# TopSolarPanel.net
KiCad netlist of a schematic drawn in EAGLE
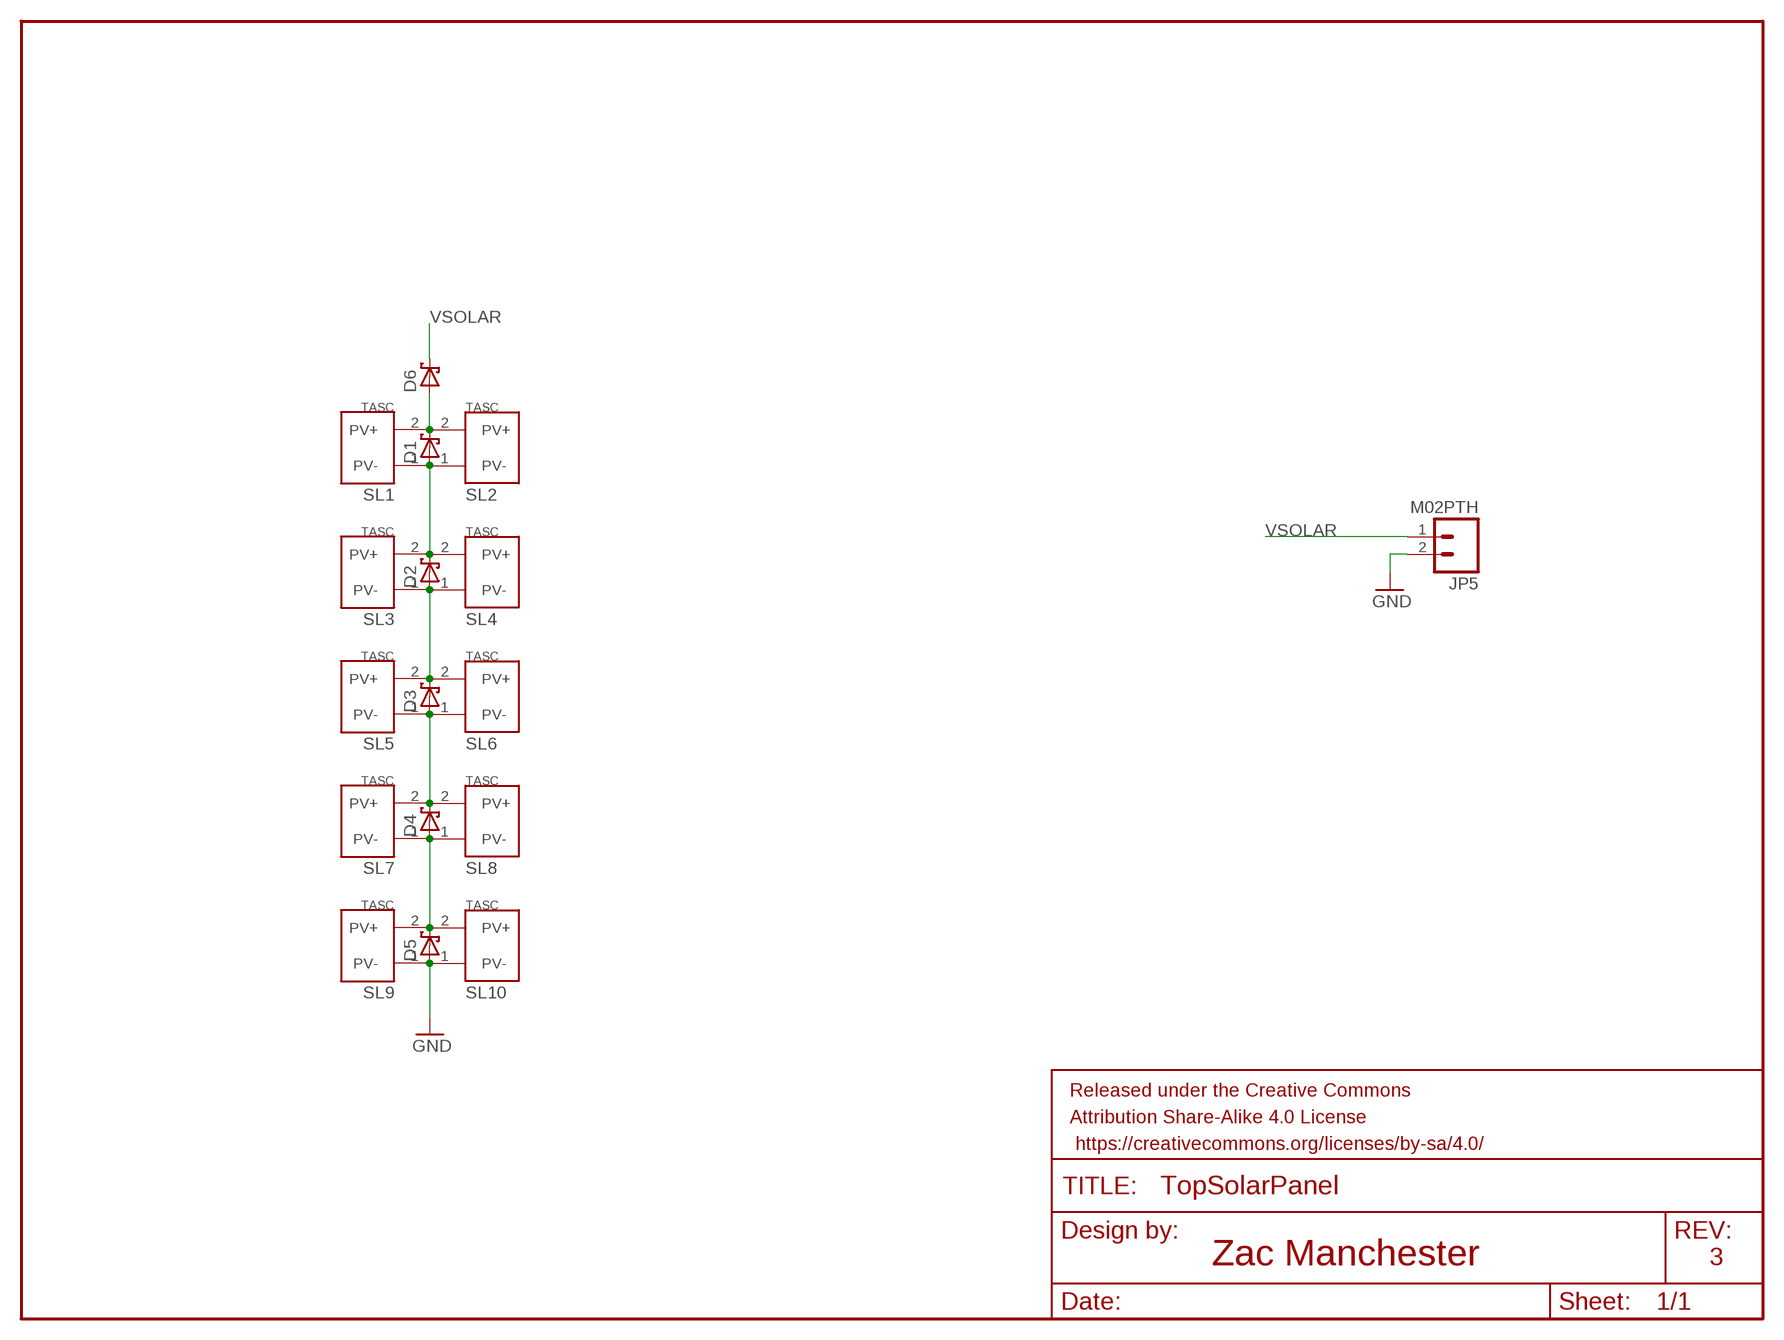
[diagram p0: schematic, sheet 1]

(export (version "E")
  (design (tool "Eeschema 10.0.6"))
  (components
    (comp (ref "D1")
      (value "SB_DIODE")
      (footprint "eagle-import:SB_DIODE")
      (libsource (lib "eagle-import") (part "SB_DIODE"))
    )
    (comp (ref "D2")
      (value "SB_DIODE")
      (footprint "eagle-import:SB_DIODE")
      (libsource (lib "eagle-import") (part "SB_DIODE"))
    )
    (comp (ref "D3")
      (value "SB_DIODE")
      (footprint "eagle-import:SB_DIODE")
      (libsource (lib "eagle-import") (part "SB_DIODE"))
    )
    (comp (ref "D4")
      (value "SB_DIODE")
      (footprint "eagle-import:SB_DIODE")
      (libsource (lib "eagle-import") (part "SB_DIODE"))
    )
    (comp (ref "D5")
      (value "SB_DIODE")
      (footprint "eagle-import:SB_DIODE")
      (libsource (lib "eagle-import") (part "SB_DIODE"))
    )
    (comp (ref "D6")
      (value "SB_DIODE")
      (footprint "eagle-import:SB_DIODE")
      (libsource (lib "eagle-import") (part "SB_DIODE"))
    )
    (comp (ref "FRAME1")
      (value "FRAME-LETTER")
      (footprint "eagle-import:CREATIVE_COMMONS")
      (libsource (lib "eagle-import") (part "FRAME-LETTER"))
    )
    (comp (ref "JP5")
      (value "M02PTH")
      (footprint "eagle-import:1X02")
      (libsource (lib "eagle-import") (part "M02PTH"))
    )
    (comp (ref "SL1")
      (value "SOLAR_CELL")
      (footprint "eagle-import:SOLAR_CELL")
      (libsource (lib "eagle-import") (part "SOLAR_CELL"))
    )
    (comp (ref "SL2")
      (value "SOLAR_CELL")
      (footprint "eagle-import:SOLAR_CELL")
      (libsource (lib "eagle-import") (part "SOLAR_CELL"))
    )
    (comp (ref "SL3")
      (value "SOLAR_CELL")
      (footprint "eagle-import:SOLAR_CELL")
      (libsource (lib "eagle-import") (part "SOLAR_CELL"))
    )
    (comp (ref "SL4")
      (value "SOLAR_CELL")
      (footprint "eagle-import:SOLAR_CELL")
      (libsource (lib "eagle-import") (part "SOLAR_CELL"))
    )
    (comp (ref "SL5")
      (value "SOLAR_CELL")
      (footprint "eagle-import:SOLAR_CELL")
      (libsource (lib "eagle-import") (part "SOLAR_CELL"))
    )
    (comp (ref "SL6")
      (value "SOLAR_CELL")
      (footprint "eagle-import:SOLAR_CELL")
      (libsource (lib "eagle-import") (part "SOLAR_CELL"))
    )
    (comp (ref "SL7")
      (value "SOLAR_CELL")
      (footprint "eagle-import:SOLAR_CELL")
      (libsource (lib "eagle-import") (part "SOLAR_CELL"))
    )
    (comp (ref "SL8")
      (value "SOLAR_CELL")
      (footprint "eagle-import:SOLAR_CELL")
      (libsource (lib "eagle-import") (part "SOLAR_CELL"))
    )
    (comp (ref "SL9")
      (value "SOLAR_CELL")
      (footprint "eagle-import:SOLAR_CELL")
      (libsource (lib "eagle-import") (part "SOLAR_CELL"))
    )
    (comp (ref "SL10")
      (value "SOLAR_CELL")
      (footprint "eagle-import:SOLAR_CELL")
      (libsource (lib "eagle-import") (part "SOLAR_CELL"))
    )
  )
  (nets
    (net (code "1") (name "/VSOLAR") (class "Default")
      (node (ref "D6") (pin "NEG") (pinfunction "NEG_NEG") (pintype "passive"))
      (node (ref "JP5") (pin "1") (pinfunction "1_1") (pintype "passive"))
    )
    (net (code "2") (name "GND") (class "Default")
      (node (ref "D5") (pin "POS") (pinfunction "POS_POS") (pintype "passive"))
      (node (ref "JP5") (pin "2") (pinfunction "2_2") (pintype "passive"))
      (node (ref "SL10") (pin "1") (pinfunction "PV-_1") (pintype "bidirectional"))
      (node (ref "SL9") (pin "1") (pinfunction "PV-_1") (pintype "bidirectional"))
    )
    (net (code "3") (name "Net-(SL1-PV+)") (class "Default")
      (node (ref "D1") (pin "NEG") (pinfunction "NEG_NEG") (pintype "passive"))
      (node (ref "D6") (pin "POS") (pinfunction "POS_POS") (pintype "passive"))
      (node (ref "SL1") (pin "2") (pinfunction "PV+_2") (pintype "bidirectional"))
      (node (ref "SL2") (pin "2") (pinfunction "PV+_2") (pintype "bidirectional"))
    )
    (net (code "4") (name "Net-(SL1-PV-)") (class "Default")
      (node (ref "D1") (pin "POS") (pinfunction "POS_POS") (pintype "passive"))
      (node (ref "D2") (pin "NEG") (pinfunction "NEG_NEG") (pintype "passive"))
      (node (ref "SL1") (pin "1") (pinfunction "PV-_1") (pintype "bidirectional"))
      (node (ref "SL2") (pin "1") (pinfunction "PV-_1") (pintype "bidirectional"))
      (node (ref "SL3") (pin "2") (pinfunction "PV+_2") (pintype "bidirectional"))
      (node (ref "SL4") (pin "2") (pinfunction "PV+_2") (pintype "bidirectional"))
    )
    (net (code "5") (name "Net-(SL3-PV-)") (class "Default")
      (node (ref "D2") (pin "POS") (pinfunction "POS_POS") (pintype "passive"))
      (node (ref "D3") (pin "NEG") (pinfunction "NEG_NEG") (pintype "passive"))
      (node (ref "SL3") (pin "1") (pinfunction "PV-_1") (pintype "bidirectional"))
      (node (ref "SL4") (pin "1") (pinfunction "PV-_1") (pintype "bidirectional"))
      (node (ref "SL5") (pin "2") (pinfunction "PV+_2") (pintype "bidirectional"))
      (node (ref "SL6") (pin "2") (pinfunction "PV+_2") (pintype "bidirectional"))
    )
    (net (code "6") (name "Net-(SL5-PV-)") (class "Default")
      (node (ref "D3") (pin "POS") (pinfunction "POS_POS") (pintype "passive"))
      (node (ref "D4") (pin "NEG") (pinfunction "NEG_NEG") (pintype "passive"))
      (node (ref "SL5") (pin "1") (pinfunction "PV-_1") (pintype "bidirectional"))
      (node (ref "SL6") (pin "1") (pinfunction "PV-_1") (pintype "bidirectional"))
      (node (ref "SL7") (pin "2") (pinfunction "PV+_2") (pintype "bidirectional"))
      (node (ref "SL8") (pin "2") (pinfunction "PV+_2") (pintype "bidirectional"))
    )
    (net (code "7") (name "Net-(SL10-PV+)") (class "Default")
      (node (ref "D4") (pin "POS") (pinfunction "POS_POS") (pintype "passive"))
      (node (ref "D5") (pin "NEG") (pinfunction "NEG_NEG") (pintype "passive"))
      (node (ref "SL10") (pin "2") (pinfunction "PV+_2") (pintype "bidirectional"))
      (node (ref "SL7") (pin "1") (pinfunction "PV-_1") (pintype "bidirectional"))
      (node (ref "SL8") (pin "1") (pinfunction "PV-_1") (pintype "bidirectional"))
      (node (ref "SL9") (pin "2") (pinfunction "PV+_2") (pintype "bidirectional"))
    )
  )
)
